# SCH_Electronic-Harp_2026-05-11.net
KiCad netlist of a schematic drawn in EasyEDA
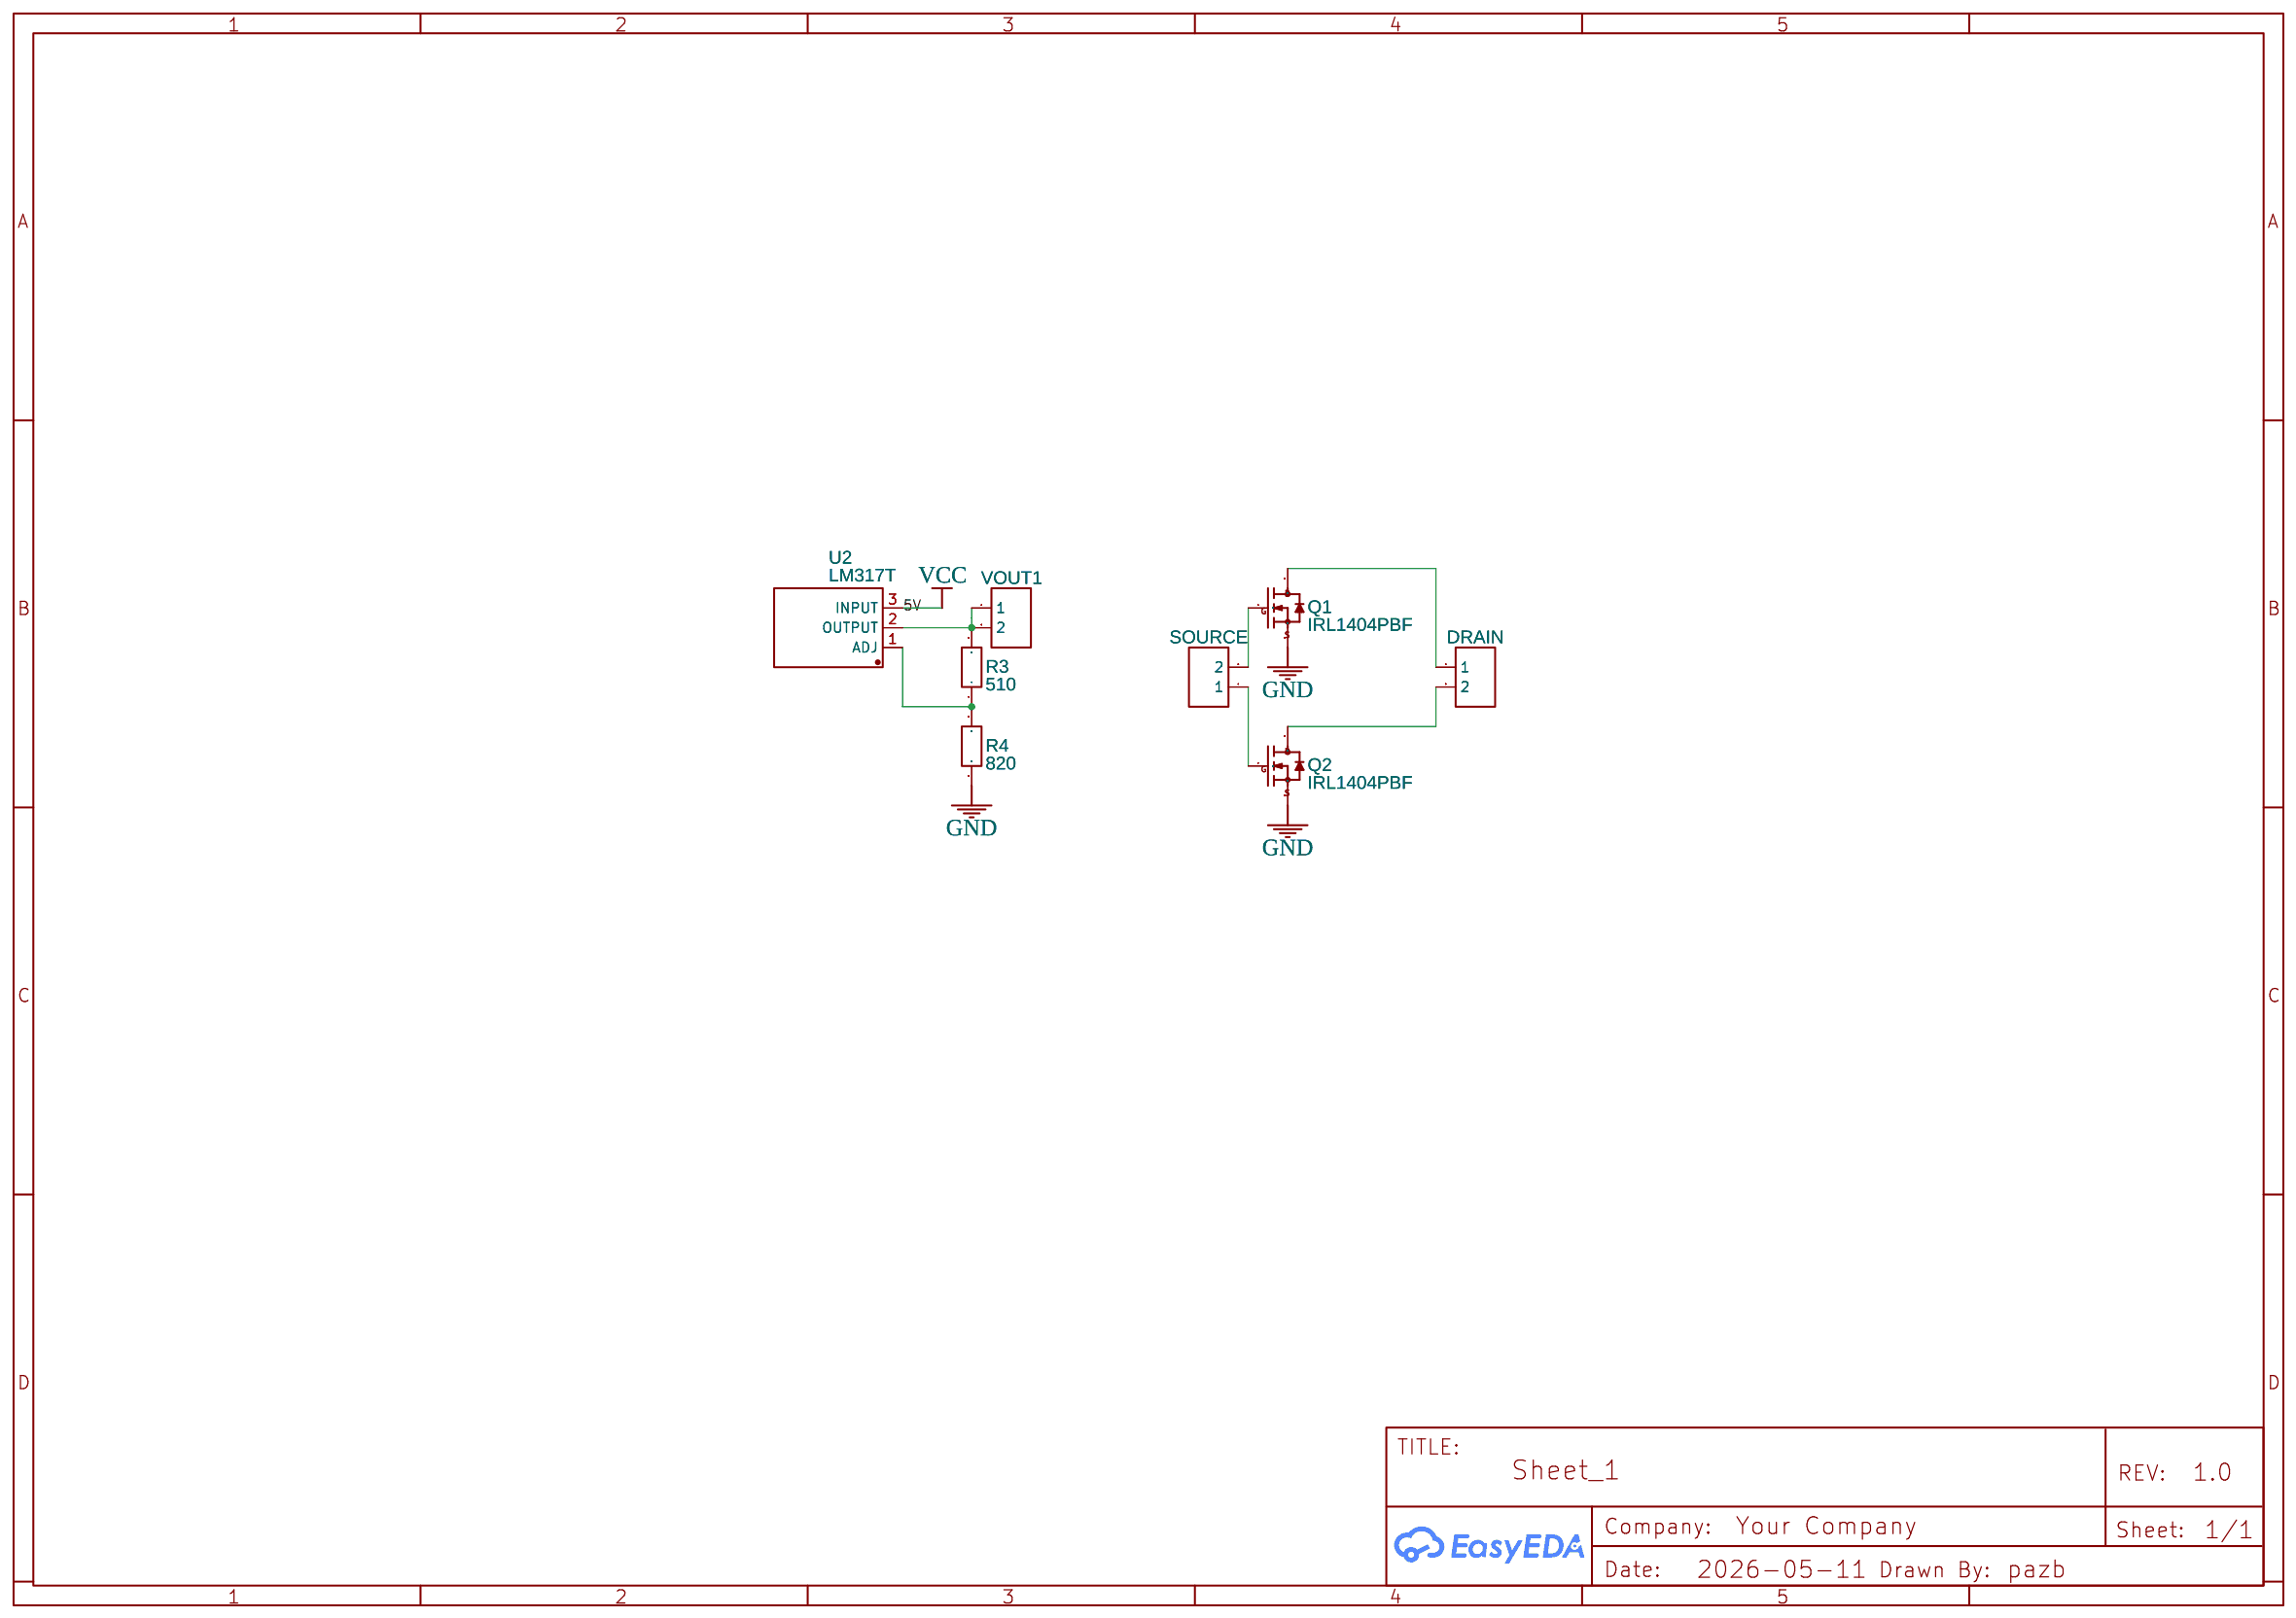
[diagram p0: schematic sheet]

(export (version "E")
  (design (tool "Eeschema 10.0.6"))
  (components
    (comp (ref "DRAIN") (value "HDR-F-2.54_1x2") (libsource (lib "") (part "HDR-F-2.54_1x2")))
    (comp (ref "Q1")
      (value "IRL1404PBF")
      (fields (field (name "Manufacturer") "Infineon(英飞凌)"))
      (libsource (lib "") (part "IRL1404PBF"))
    )
    (comp (ref "Q2")
      (value "IRL1404PBF")
      (fields (field (name "Manufacturer") "Infineon(英飞凌)"))
      (libsource (lib "") (part "IRL1404PBF"))
    )
    (comp (ref "R3") (value "510") (libsource (lib "") (part "R_0603_EU")))
    (comp (ref "R4") (value "820") (libsource (lib "") (part "R_0603_EU")))
    (comp (ref "SOURCE") (value "HDR-F-2.54_1x2") (libsource (lib "") (part "HDR-F-2.54_1x2_2")))
    (comp (ref "U2")
      (value "LM317T")
      (fields (field (name "Manufacturer") "ST(意法半导体)"))
      (libsource (lib "") (part "LM317T"))
    )
    (comp (ref "VOUT1") (value "HDR-F-2.54_1x2") (libsource (lib "") (part "HDR-F-2.54_1x2_1")))
  )
  (nets
    (net (code "1") (name "GND") (class "Default")
      (node (ref "Q1") (pin "3") (pinfunction "S_3") (pintype "unspecified"))
      (node (ref "Q2") (pin "3") (pinfunction "S_3") (pintype "unspecified"))
      (node (ref "R4") (pin "1") (pinfunction "1_1") (pintype "unspecified"))
    )
    (net (code "2") (name "Net-(Q1-D)") (class "Default")
      (node (ref "DRAIN") (pin "1") (pinfunction "1_1") (pintype "input"))
      (node (ref "Q1") (pin "2") (pinfunction "D_2") (pintype "unspecified"))
    )
    (net (code "3") (name "Net-(Q1-G)") (class "Default")
      (node (ref "Q1") (pin "1") (pinfunction "G_1") (pintype "unspecified"))
      (node (ref "SOURCE") (pin "2") (pinfunction "2_2") (pintype "input"))
    )
    (net (code "4") (name "Net-(Q2-D)") (class "Default")
      (node (ref "DRAIN") (pin "2") (pinfunction "2_2") (pintype "input"))
      (node (ref "Q2") (pin "2") (pinfunction "D_2") (pintype "unspecified"))
    )
    (net (code "5") (name "Net-(Q2-G)") (class "Default")
      (node (ref "Q2") (pin "1") (pinfunction "G_1") (pintype "unspecified"))
      (node (ref "SOURCE") (pin "1") (pinfunction "1_1") (pintype "input"))
    )
    (net (code "6") (name "Net-(U2-ADJ)") (class "Default")
      (node (ref "R3") (pin "1") (pinfunction "1_1") (pintype "unspecified"))
      (node (ref "R4") (pin "2") (pinfunction "2_2") (pintype "unspecified"))
      (node (ref "U2") (pin "1") (pinfunction "ADJ_1") (pintype "unspecified"))
    )
    (net (code "7") (name "Net-(U2-OUTPUT)") (class "Default")
      (node (ref "R3") (pin "2") (pinfunction "2_2") (pintype "unspecified"))
      (node (ref "U2") (pin "2") (pinfunction "OUTPUT_2") (pintype "unspecified"))
      (node (ref "VOUT1") (pin "1") (pinfunction "1_1") (pintype "input"))
      (node (ref "VOUT1") (pin "2") (pinfunction "2_2") (pintype "input"))
    )
    (net (code "8") (name "VCC") (class "Default")
      (node (ref "U2") (pin "3") (pinfunction "INPUT_3") (pintype "unspecified"))
    )
  )
)
